# pwm_module.net
KiCad netlist of a schematic drawn in EAGLE
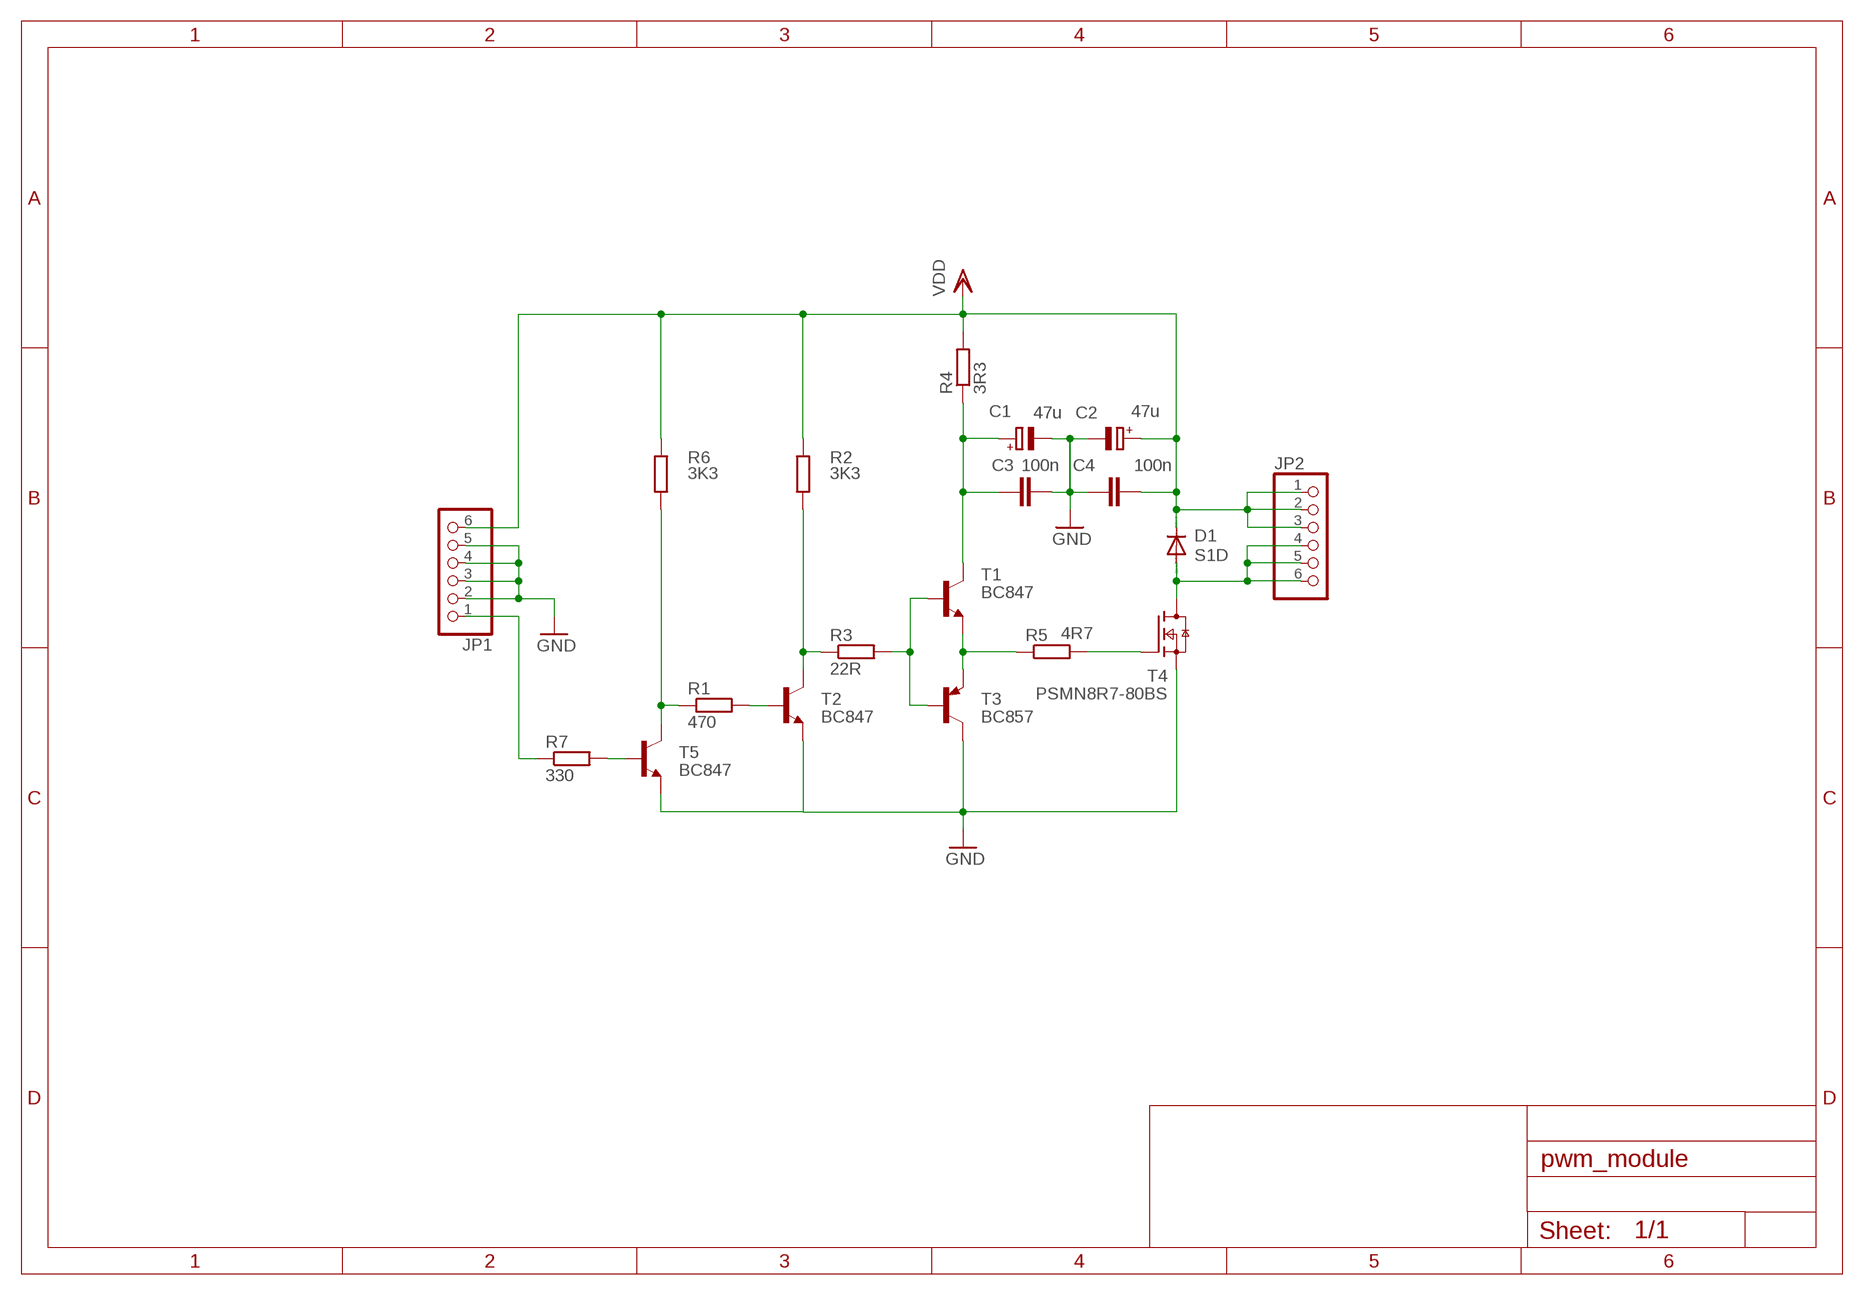
[diagram p0: schematic, sheet 1]

(export (version "E")
  (design (tool "Eeschema 10.0.6"))
  (components
    (comp (ref "C1")
      (value "47u")
      (footprint "eagle-import:PANASONIC_F")
      (libsource (lib "eagle-import") (part "CPOL-EUF"))
    )
    (comp (ref "C2")
      (value "47u")
      (footprint "eagle-import:PANASONIC_F")
      (libsource (lib "eagle-import") (part "CPOL-EUF"))
    )
    (comp (ref "C3")
      (value "100n")
      (footprint "eagle-import:C1206K")
      (libsource (lib "eagle-import") (part "C-EUC1206K"))
    )
    (comp (ref "C4")
      (value "100n")
      (footprint "eagle-import:C1206K")
      (libsource (lib "eagle-import") (part "C-EUC1206K"))
    )
    (comp (ref "D1")
      (value "S1D")
      (footprint "eagle-import:DO-214AC")
      (libsource (lib "eagle-import") (part "DIODE-DO-214AC"))
    )
    (comp (ref "JP1")
      (value "PINHD-1X6")
      (footprint "eagle-import:1X06")
      (libsource (lib "eagle-import") (part "PINHD-1X6"))
    )
    (comp (ref "JP2")
      (value "PINHD-1X6")
      (footprint "eagle-import:1X06")
      (libsource (lib "eagle-import") (part "PINHD-1X6"))
    )
    (comp (ref "R1")
      (value "470")
      (footprint "eagle-import:M0805")
      (libsource (lib "eagle-import") (part "R-EU_M0805"))
    )
    (comp (ref "R2")
      (value "3K3")
      (footprint "eagle-import:M0805")
      (libsource (lib "eagle-import") (part "R-EU_M0805"))
    )
    (comp (ref "R3")
      (value "22R")
      (footprint "eagle-import:M0805")
      (libsource (lib "eagle-import") (part "R-EU_M0805"))
    )
    (comp (ref "R4")
      (value "3R3")
      (footprint "eagle-import:M0805")
      (libsource (lib "eagle-import") (part "R-EU_M0805"))
    )
    (comp (ref "R5")
      (value "4R7")
      (footprint "eagle-import:M0805")
      (libsource (lib "eagle-import") (part "R-EU_M0805"))
    )
    (comp (ref "R6")
      (value "3K3")
      (footprint "eagle-import:M0805")
      (libsource (lib "eagle-import") (part "R-EU_M0805"))
    )
    (comp (ref "R7")
      (value "330")
      (footprint "eagle-import:M0805")
      (libsource (lib "eagle-import") (part "R-EU_M0805"))
    )
    (comp (ref "T1")
      (value "BC847")
      (footprint "eagle-import:SOT23")
      (libsource (lib "eagle-import") (part "BC847"))
    )
    (comp (ref "T2")
      (value "BC847")
      (footprint "eagle-import:SOT23")
      (libsource (lib "eagle-import") (part "BC847"))
    )
    (comp (ref "T3")
      (value "BC857")
      (footprint "eagle-import:SOT23-BEC")
      (libsource (lib "eagle-import") (part "-PNP-SOT23-BECBC857A"))
    )
    (comp (ref "T4")
      (value "PSMN8R7-80BS")
      (footprint "eagle-import:SOT404")
      (libsource (lib "eagle-import") (part "BUK761R3-30E"))
    )
    (comp (ref "T5")
      (value "BC847")
      (footprint "eagle-import:SOT23")
      (libsource (lib "eagle-import") (part "BC847"))
    )
  )
  (nets
    (net (code "1") (name "GND") (class "Default")
      (node (ref "C1") (pin "-") (pinfunction "-_-") (pintype "passive"))
      (node (ref "C2") (pin "-") (pinfunction "-_-") (pintype "passive"))
      (node (ref "C3") (pin "2") (pinfunction "2_2") (pintype "passive"))
      (node (ref "C4") (pin "2") (pinfunction "2_2") (pintype "passive"))
      (node (ref "JP1") (pin "2") (pinfunction "2_2") (pintype "passive"))
      (node (ref "JP1") (pin "3") (pinfunction "3_3") (pintype "passive"))
      (node (ref "JP1") (pin "4") (pinfunction "4_4") (pintype "passive"))
      (node (ref "JP1") (pin "5") (pinfunction "5_5") (pintype "passive"))
      (node (ref "T2") (pin "2") (pinfunction "E_2") (pintype "passive"))
      (node (ref "T3") (pin "C") (pinfunction "C_C") (pintype "passive"))
      (node (ref "T4") (pin "3") (pinfunction "S_3") (pintype "passive"))
      (node (ref "T5") (pin "2") (pinfunction "E_2") (pintype "passive"))
    )
    (net (code "2") (name "Net-(JP1-Pad1)") (class "Default")
      (node (ref "JP1") (pin "1") (pinfunction "1_1") (pintype "passive"))
      (node (ref "R7") (pin "1") (pinfunction "1_1") (pintype "passive"))
    )
    (net (code "3") (name "Net-(T1-B)") (class "Default")
      (node (ref "R3") (pin "2") (pinfunction "2_2") (pintype "passive"))
      (node (ref "T1") (pin "1") (pinfunction "B_1") (pintype "passive"))
      (node (ref "T3") (pin "B") (pinfunction "B_B") (pintype "passive"))
    )
    (net (code "4") (name "Net-(T1-C)") (class "Default")
      (node (ref "C1") (pin "+") (pinfunction "+_+") (pintype "passive"))
      (node (ref "C3") (pin "1") (pinfunction "1_1") (pintype "passive"))
      (node (ref "R4") (pin "1") (pinfunction "1_1") (pintype "passive"))
      (node (ref "T1") (pin "3") (pinfunction "C_3") (pintype "passive"))
    )
    (net (code "5") (name "Net-(T1-E)") (class "Default")
      (node (ref "R5") (pin "1") (pinfunction "1_1") (pintype "passive"))
      (node (ref "T1") (pin "2") (pinfunction "E_2") (pintype "passive"))
      (node (ref "T3") (pin "E") (pinfunction "E_E") (pintype "passive"))
    )
    (net (code "6") (name "Net-(T2-B)") (class "Default")
      (node (ref "R1") (pin "2") (pinfunction "2_2") (pintype "passive"))
      (node (ref "T2") (pin "1") (pinfunction "B_1") (pintype "passive"))
    )
    (net (code "7") (name "Net-(T2-C)") (class "Default")
      (node (ref "R2") (pin "1") (pinfunction "1_1") (pintype "passive"))
      (node (ref "R3") (pin "1") (pinfunction "1_1") (pintype "passive"))
      (node (ref "T2") (pin "3") (pinfunction "C_3") (pintype "passive"))
    )
    (net (code "8") (name "Net-(T4-D)") (class "Default")
      (node (ref "D1") (pin "A") (pinfunction "A_A") (pintype "passive"))
      (node (ref "JP2") (pin "4") (pinfunction "4_4") (pintype "passive"))
      (node (ref "JP2") (pin "5") (pinfunction "5_5") (pintype "passive"))
      (node (ref "JP2") (pin "6") (pinfunction "6_6") (pintype "passive"))
      (node (ref "T4") (pin "MB") (pinfunction "D_MB") (pintype "passive"))
    )
    (net (code "9") (name "Net-(T4-G)") (class "Default")
      (node (ref "R5") (pin "2") (pinfunction "2_2") (pintype "passive"))
      (node (ref "T4") (pin "1") (pinfunction "G_1") (pintype "passive"))
    )
    (net (code "10") (name "Net-(T5-B)") (class "Default")
      (node (ref "R7") (pin "2") (pinfunction "2_2") (pintype "passive"))
      (node (ref "T5") (pin "1") (pinfunction "B_1") (pintype "passive"))
    )
    (net (code "11") (name "Net-(T5-C)") (class "Default")
      (node (ref "R1") (pin "1") (pinfunction "1_1") (pintype "passive"))
      (node (ref "R6") (pin "1") (pinfunction "1_1") (pintype "passive"))
      (node (ref "T5") (pin "3") (pinfunction "C_3") (pintype "passive"))
    )
    (net (code "12") (name "VDD") (class "Default")
      (node (ref "C2") (pin "+") (pinfunction "+_+") (pintype "passive"))
      (node (ref "C4") (pin "1") (pinfunction "1_1") (pintype "passive"))
      (node (ref "D1") (pin "C") (pinfunction "C_C") (pintype "passive"))
      (node (ref "JP1") (pin "6") (pinfunction "6_6") (pintype "passive"))
      (node (ref "JP2") (pin "1") (pinfunction "1_1") (pintype "passive"))
      (node (ref "JP2") (pin "2") (pinfunction "2_2") (pintype "passive"))
      (node (ref "JP2") (pin "3") (pinfunction "3_3") (pintype "passive"))
      (node (ref "R2") (pin "2") (pinfunction "2_2") (pintype "passive"))
      (node (ref "R4") (pin "2") (pinfunction "2_2") (pintype "passive"))
      (node (ref "R6") (pin "2") (pinfunction "2_2") (pintype "passive"))
    )
  )
)
